# eagle.net
KiCad netlist of a schematic drawn in EAGLE
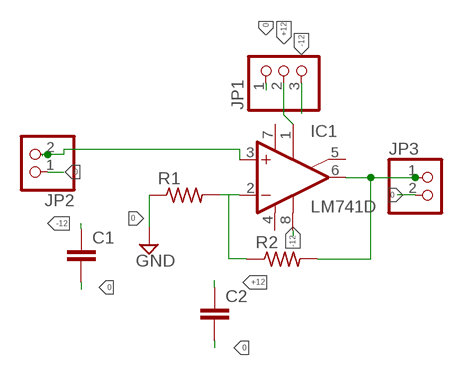
[diagram p0: schematic, sheet 1]

(export (version "E")
  (design (tool "Eeschema 10.0.6"))
  (components
    (comp (ref "C1")
      (value "C-EU050-025X075")
      (footprint "eagle-import:C050-025X075")
      (libsource (lib "eagle-import") (part "C-EU050-025X075"))
    )
    (comp (ref "C2")
      (value "C-EU050-025X075")
      (footprint "eagle-import:C050-025X075")
      (libsource (lib "eagle-import") (part "C-EU050-025X075"))
    )
    (comp (ref "IC1")
      (value "LM741D")
      (footprint "eagle-import:SO08")
      (libsource (lib "eagle-import") (part "741DLM"))
    )
    (comp (ref "JP1")
      (value "PINHD-1X3")
      (footprint "eagle-import:1X03")
      (libsource (lib "eagle-import") (part "PINHD-1X3"))
    )
    (comp (ref "JP2")
      (value "PINHD-1X2")
      (footprint "eagle-import:1X02")
      (libsource (lib "eagle-import") (part "PINHD-1X2"))
    )
    (comp (ref "JP3")
      (value "PINHD-1X2")
      (footprint "eagle-import:1X02")
      (libsource (lib "eagle-import") (part "PINHD-1X2"))
    )
    (comp (ref "R1")
      (value "R-US_0207/10")
      (footprint "eagle-import:0207_10")
      (libsource (lib "eagle-import") (part "R-US_0207/10"))
    )
    (comp (ref "R2")
      (value "R-US_0207/10")
      (footprint "eagle-import:0207_10")
      (libsource (lib "eagle-import") (part "R-US_0207/10"))
    )
  )
  (nets
    (net (code "1") (name "+12") (class "Default")
      (node (ref "C2") (pin "1") (pinfunction "1_1") (pintype "passive"))
      (node (ref "IC1") (pin "1") (pinfunction "ON1_1") (pintype "passive"))
      (node (ref "JP1") (pin "2") (pinfunction "2_2") (pintype "passive"))
    )
    (net (code "2") (name "-12") (class "Default")
      (node (ref "C1") (pin "1") (pinfunction "1_1") (pintype "passive"))
      (node (ref "IC1") (pin "8") (pinfunction "OPT_8") (pintype "passive"))
      (node (ref "JP1") (pin "3") (pinfunction "3_3") (pintype "passive"))
    )
    (net (code "3") (name "/V+") (class "Default")
      (node (ref "IC1") (pin "7") (pinfunction "V+_7") (pintype "power_in"))
    )
    (net (code "4") (name "/V-") (class "Default")
      (node (ref "IC1") (pin "4") (pinfunction "V-_4") (pintype "power_in"))
    )
    (net (code "5") (name "0") (class "Default")
      (node (ref "C1") (pin "2") (pinfunction "2_2") (pintype "passive"))
      (node (ref "C2") (pin "2") (pinfunction "2_2") (pintype "passive"))
      (node (ref "JP1") (pin "1") (pinfunction "1_1") (pintype "passive"))
      (node (ref "JP2") (pin "1") (pinfunction "1_1") (pintype "passive"))
      (node (ref "JP3") (pin "2") (pinfunction "2_2") (pintype "passive"))
      (node (ref "R1") (pin "1") (pinfunction "1_1") (pintype "passive"))
    )
    (net (code "6") (name "Net-(IC1-+IN)") (class "Default")
      (node (ref "IC1") (pin "3") (pinfunction "+IN_3") (pintype "input"))
      (node (ref "JP2") (pin "2") (pinfunction "2_2") (pintype "passive"))
    )
    (net (code "7") (name "Net-(IC1--IN)") (class "Default")
      (node (ref "IC1") (pin "2") (pinfunction "-IN_2") (pintype "input"))
      (node (ref "R1") (pin "2") (pinfunction "2_2") (pintype "passive"))
      (node (ref "R2") (pin "1") (pinfunction "1_1") (pintype "passive"))
    )
    (net (code "8") (name "Net-(IC1-OUT)") (class "Default")
      (node (ref "IC1") (pin "6") (pinfunction "OUT_6") (pintype "output"))
      (node (ref "JP3") (pin "1") (pinfunction "1_1") (pintype "passive"))
      (node (ref "R2") (pin "2") (pinfunction "2_2") (pintype "passive"))
    )
    (net (code "9") (name "unconnected-(IC1-ON2-Pad5)") (class "Default")
      (node (ref "IC1") (pin "5") (pinfunction "ON2_5") (pintype "passive"))
    )
  )
)
